# 3Phase_Inverter2.net
KiCad netlist of a schematic drawn in Altium Designer
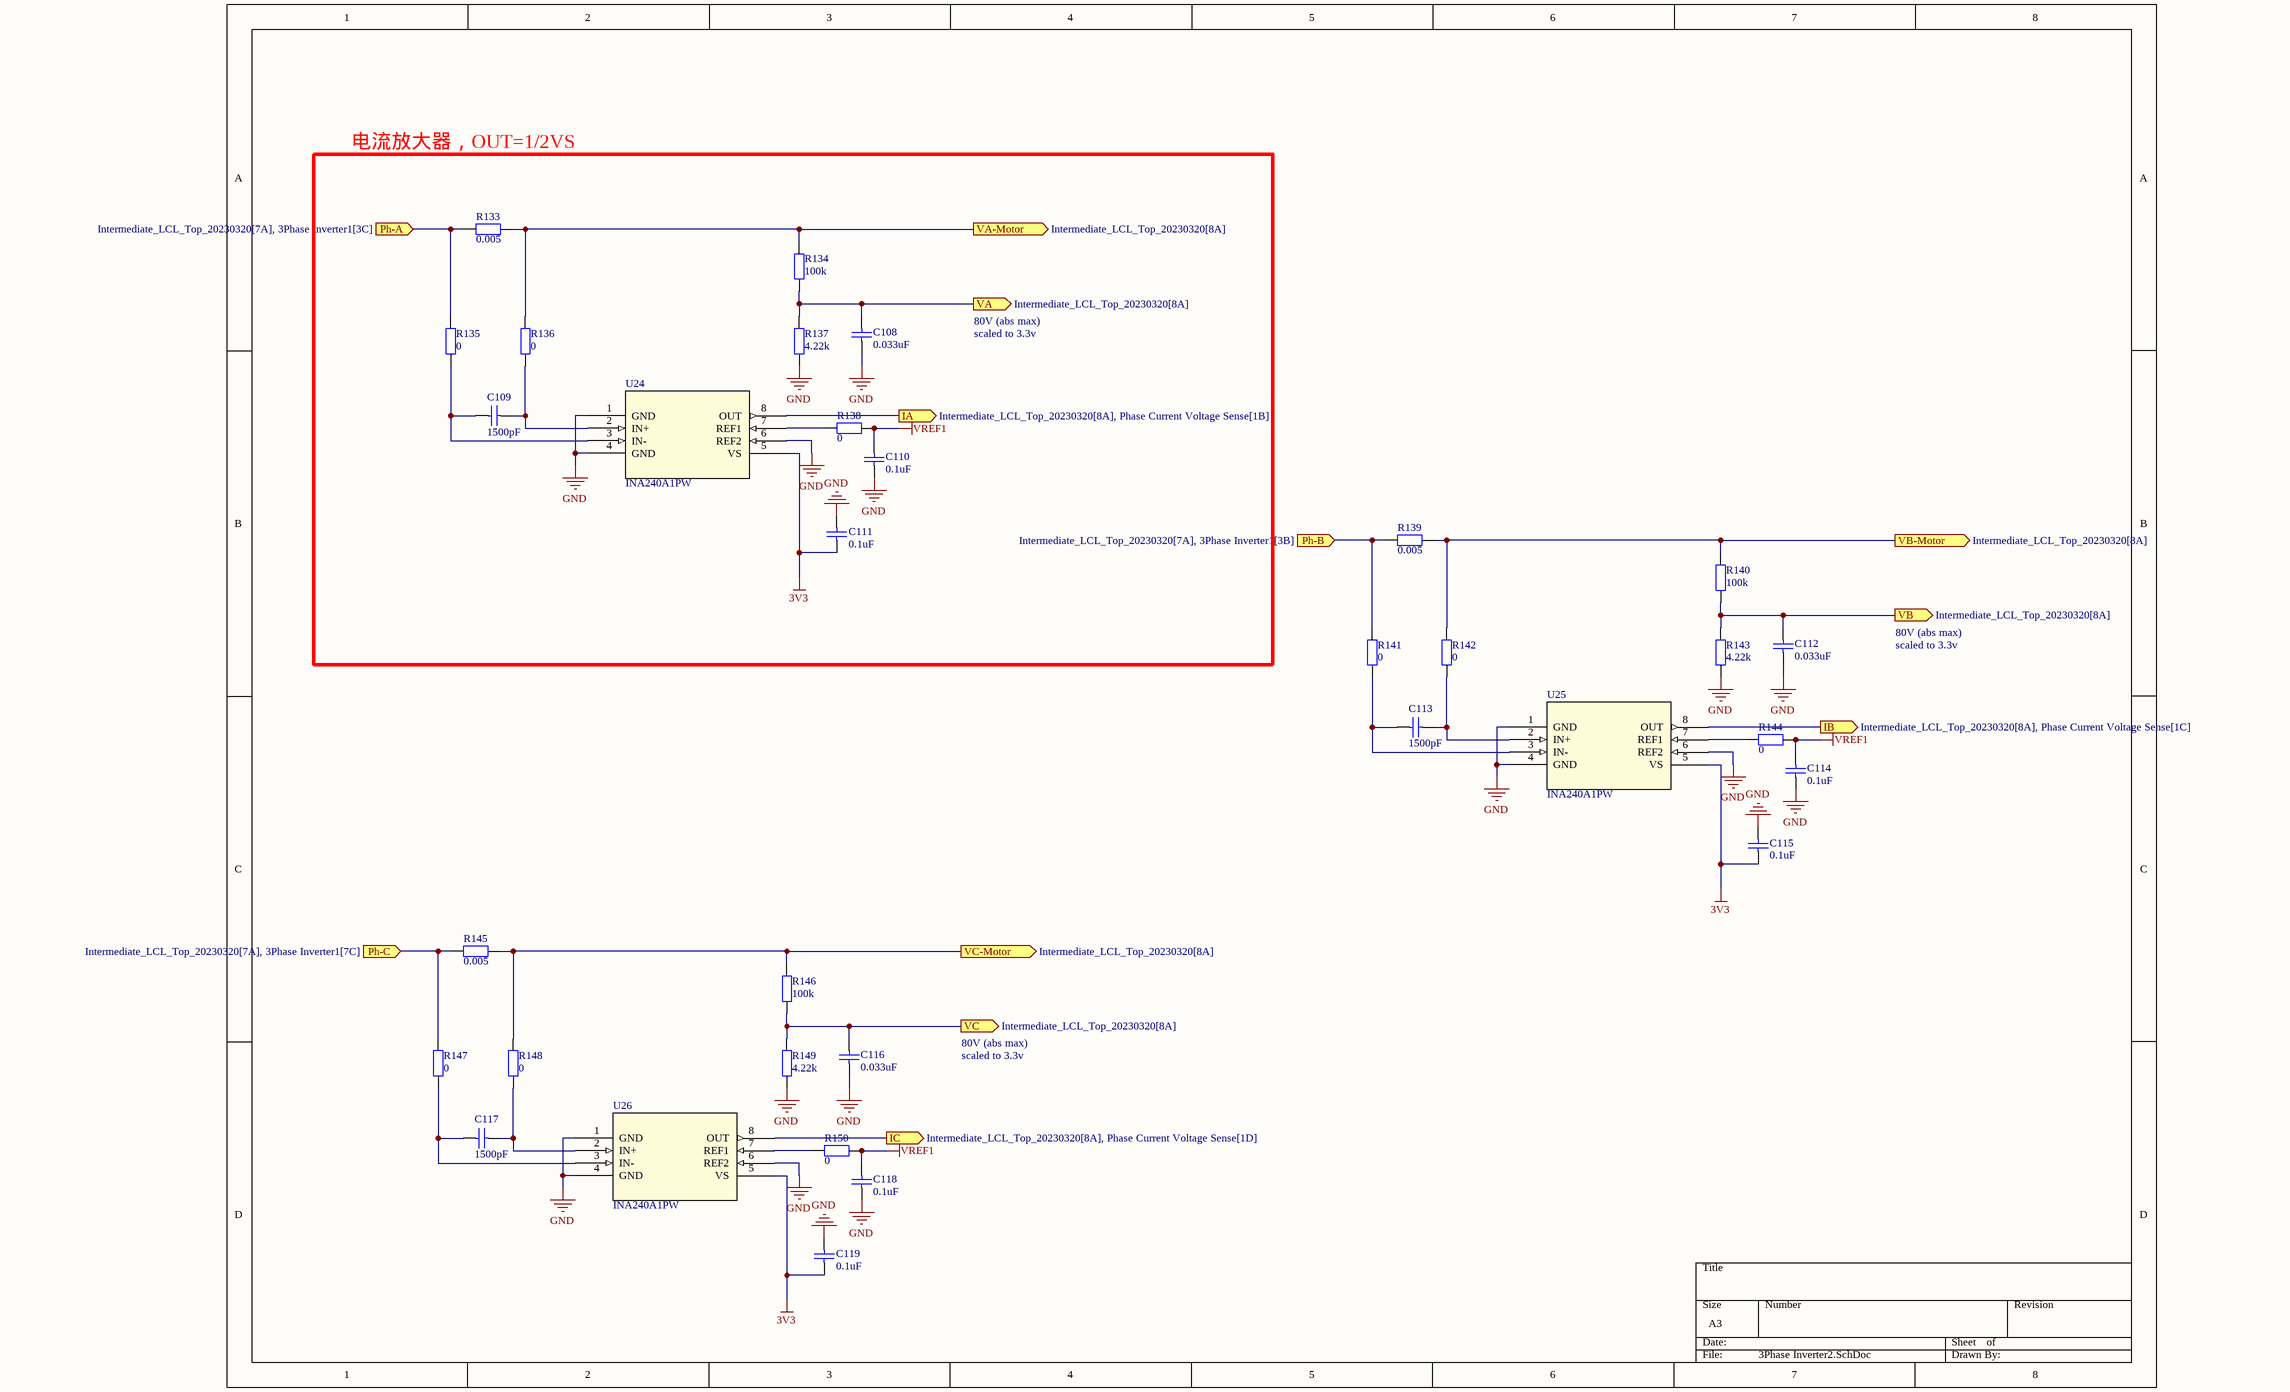
[diagram p0: 3Phase Inverter2.SchDoc]

(export (version "E")
  (design (tool "Eeschema 10.0.6"))
  (components
    (comp (ref "C108")
      (value "0.033uF")
      (footprint "CAPC1608X06N")
      (description "Capacitor")
      (fields (field (name "PUBLISHER") "Altium Limited"))
      (libsource (lib "Simscale") (part "Cap"))
    )
    (comp (ref "C109")
      (value "1500pF")
      (footprint "CAPC1608X06N")
      (description "Capacitor")
      (fields (field (name "PUBLISHER") "Altium Limited"))
      (libsource (lib "Simscale") (part "Cap"))
    )
    (comp (ref "C110")
      (value "0.1uF")
      (footprint "CAPC1608X06N")
      (description "Capacitor")
      (fields (field (name "PUBLISHER") "Altium Limited"))
      (libsource (lib "Simscale") (part "Cap"))
    )
    (comp (ref "C111")
      (value "0.1uF")
      (footprint "CAPC1608X06N")
      (description "Capacitor")
      (fields (field (name "PUBLISHER") "Altium Limited"))
      (libsource (lib "Simscale") (part "Cap"))
    )
    (comp (ref "C112")
      (value "0.033uF")
      (footprint "CAPC1608X06N")
      (description "Capacitor")
      (fields (field (name "PUBLISHER") "Altium Limited"))
      (libsource (lib "Simscale") (part "Cap"))
    )
    (comp (ref "C113")
      (value "1500pF")
      (footprint "CAPC1608X06N")
      (description "Capacitor")
      (fields (field (name "PUBLISHER") "Altium Limited"))
      (libsource (lib "Simscale") (part "Cap"))
    )
    (comp (ref "C114")
      (value "0.1uF")
      (footprint "CAPC1608X06N")
      (description "Capacitor")
      (fields (field (name "PUBLISHER") "Altium Limited"))
      (libsource (lib "Simscale") (part "Cap"))
    )
    (comp (ref "C115")
      (value "0.1uF")
      (footprint "CAPC1608X06N")
      (description "Capacitor")
      (fields (field (name "PUBLISHER") "Altium Limited"))
      (libsource (lib "Simscale") (part "Cap"))
    )
    (comp (ref "C116")
      (value "0.033uF")
      (footprint "CAPC1608X06N")
      (description "Capacitor")
      (fields (field (name "PUBLISHER") "Altium Limited"))
      (libsource (lib "Simscale") (part "Cap"))
    )
    (comp (ref "C117")
      (value "1500pF")
      (footprint "CAPC1608X06N")
      (description "Capacitor")
      (fields (field (name "PUBLISHER") "Altium Limited"))
      (libsource (lib "Simscale") (part "Cap"))
    )
    (comp (ref "C118")
      (value "0.1uF")
      (footprint "CAPC1608X06N")
      (description "Capacitor")
      (fields (field (name "PUBLISHER") "Altium Limited"))
      (libsource (lib "Simscale") (part "Cap"))
    )
    (comp (ref "C119")
      (value "0.1uF")
      (footprint "CAPC1608X06N")
      (description "Capacitor")
      (fields (field (name "PUBLISHER") "Altium Limited"))
      (libsource (lib "Simscale") (part "Cap"))
    )
    (comp (ref "R133")
      (value "0.005")
      (footprint "RESC1608X05N")
      (description "贴片电阻")
      (libsource (lib "") (part "0603 100KΩ (1003) 1%_4_2"))
    )
    (comp (ref "R134")
      (value "100k")
      (footprint "RESC1608X05N")
      (description "贴片电阻")
      (libsource (lib "") (part "0603 100KΩ (1003) 1%_4_1"))
    )
    (comp (ref "R135")
      (value "0")
      (footprint "RESC1608X05N")
      (description "贴片电阻")
      (libsource (lib "Simscale") (part "0603 100KΩ (1003) 1%_4"))
    )
    (comp (ref "R136")
      (value "0")
      (footprint "RESC1608X05N")
      (description "贴片电阻")
      (libsource (lib "Simscale") (part "0603 100KΩ (1003) 1%_4"))
    )
    (comp (ref "R137")
      (value "4.22k")
      (footprint "RESC1608X05N")
      (description "贴片电阻")
      (libsource (lib "") (part "0603 100KΩ (1003) 1%_4_1"))
    )
    (comp (ref "R138")
      (value "0")
      (footprint "RESC1608X05N")
      (description "贴片电阻")
      (libsource (lib "") (part "0603 100KΩ (1003) 1%_4_2"))
    )
    (comp (ref "R139")
      (value "0.005")
      (footprint "RESC1608X05N")
      (description "贴片电阻")
      (libsource (lib "") (part "0603 100KΩ (1003) 1%_4_2"))
    )
    (comp (ref "R140")
      (value "100k")
      (footprint "RESC1608X05N")
      (description "贴片电阻")
      (libsource (lib "") (part "0603 100KΩ (1003) 1%_4_1"))
    )
    (comp (ref "R141")
      (value "0")
      (footprint "RESC1608X05N")
      (description "贴片电阻")
      (libsource (lib "Simscale") (part "0603 100KΩ (1003) 1%_4"))
    )
    (comp (ref "R142")
      (value "0")
      (footprint "RESC1608X05N")
      (description "贴片电阻")
      (libsource (lib "Simscale") (part "0603 100KΩ (1003) 1%_4"))
    )
    (comp (ref "R143")
      (value "4.22k")
      (footprint "RESC1608X05N")
      (description "贴片电阻")
      (libsource (lib "") (part "0603 100KΩ (1003) 1%_4_1"))
    )
    (comp (ref "R144")
      (value "0")
      (footprint "RESC1608X05N")
      (description "贴片电阻")
      (libsource (lib "") (part "0603 100KΩ (1003) 1%_4_2"))
    )
    (comp (ref "R145")
      (value "0.005")
      (footprint "RESC1608X05N")
      (description "贴片电阻")
      (libsource (lib "") (part "0603 100KΩ (1003) 1%_4_2"))
    )
    (comp (ref "R146")
      (value "100k")
      (footprint "RESC1608X05N")
      (description "贴片电阻")
      (libsource (lib "") (part "0603 100KΩ (1003) 1%_4_1"))
    )
    (comp (ref "R147")
      (value "0")
      (footprint "RESC1608X05N")
      (description "贴片电阻")
      (libsource (lib "Simscale") (part "0603 100KΩ (1003) 1%_4"))
    )
    (comp (ref "R148")
      (value "0")
      (footprint "RESC1608X05N")
      (description "贴片电阻")
      (libsource (lib "Simscale") (part "0603 100KΩ (1003) 1%_4"))
    )
    (comp (ref "R149")
      (value "4.22k")
      (footprint "RESC1608X05N")
      (description "贴片电阻")
      (libsource (lib "") (part "0603 100KΩ (1003) 1%_4_1"))
    )
    (comp (ref "R150")
      (value "0")
      (footprint "RESC1608X05N")
      (description "贴片电阻")
      (libsource (lib "") (part "0603 100KΩ (1003) 1%_4_2"))
    )
    (comp (ref "U24")
      (value "INA240A1PW")
      (footprint "PW0008A_N_TEX")
      (description "No Description Available")
      (fields (field (name "COPYRIGHT") "Copyright (C) 2024 Ultra Librarian. All rights reserved."))
      (libsource (lib "aaa1") (part "INA240A1PW"))
    )
    (comp (ref "U25")
      (value "INA240A1PW")
      (footprint "PW0008A_N_TEX")
      (description "No Description Available")
      (fields (field (name "COPYRIGHT") "Copyright (C) 2024 Ultra Librarian. All rights reserved."))
      (libsource (lib "aaa1") (part "INA240A1PW"))
    )
    (comp (ref "U26")
      (value "INA240A1PW")
      (footprint "PW0008A_N_TEX")
      (description "No Description Available")
      (fields (field (name "COPYRIGHT") "Copyright (C) 2024 Ultra Librarian. All rights reserved."))
      (libsource (lib "aaa1") (part "INA240A1PW"))
    )
  )
  (nets
    (net (code "1") (name "/IA") (class "Default")
      (node (ref "U24") (pin "8") (pinfunction "OUT_8") (pintype "output"))
    )
    (net (code "2") (name "/IB") (class "Default")
      (node (ref "U25") (pin "8") (pinfunction "OUT_8") (pintype "output"))
    )
    (net (code "3") (name "/IC") (class "Default")
      (node (ref "U26") (pin "8") (pinfunction "OUT_8") (pintype "output"))
    )
    (net (code "4") (name "/Ph-A") (class "Default")
      (node (ref "R133") (pin "2") (pinfunction "2_2") (pintype "passive"))
      (node (ref "R135") (pin "1") (pinfunction "1_1") (pintype "passive"))
    )
    (net (code "5") (name "/Ph-B") (class "Default")
      (node (ref "R139") (pin "2") (pinfunction "2_2") (pintype "passive"))
      (node (ref "R141") (pin "1") (pinfunction "1_1") (pintype "passive"))
    )
    (net (code "6") (name "/Ph-C") (class "Default")
      (node (ref "R145") (pin "2") (pinfunction "2_2") (pintype "passive"))
      (node (ref "R147") (pin "1") (pinfunction "1_1") (pintype "passive"))
    )
    (net (code "7") (name "/VA") (class "Default")
      (node (ref "C108") (pin "1") (pinfunction "1_1") (pintype "passive"))
      (node (ref "R134") (pin "1") (pinfunction "1_1") (pintype "passive"))
      (node (ref "R137") (pin "2") (pinfunction "2_2") (pintype "passive"))
    )
    (net (code "8") (name "/VA-Motor") (class "Default")
      (node (ref "R133") (pin "1") (pinfunction "1_1") (pintype "passive"))
      (node (ref "R134") (pin "2") (pinfunction "2_2") (pintype "passive"))
      (node (ref "R136") (pin "1") (pinfunction "1_1") (pintype "passive"))
    )
    (net (code "9") (name "/VB") (class "Default")
      (node (ref "C112") (pin "1") (pinfunction "1_1") (pintype "passive"))
      (node (ref "R140") (pin "1") (pinfunction "1_1") (pintype "passive"))
      (node (ref "R143") (pin "2") (pinfunction "2_2") (pintype "passive"))
    )
    (net (code "10") (name "/VB-Motor") (class "Default")
      (node (ref "R139") (pin "1") (pinfunction "1_1") (pintype "passive"))
      (node (ref "R140") (pin "2") (pinfunction "2_2") (pintype "passive"))
      (node (ref "R142") (pin "1") (pinfunction "1_1") (pintype "passive"))
    )
    (net (code "11") (name "/VC") (class "Default")
      (node (ref "C116") (pin "1") (pinfunction "1_1") (pintype "passive"))
      (node (ref "R146") (pin "1") (pinfunction "1_1") (pintype "passive"))
      (node (ref "R149") (pin "2") (pinfunction "2_2") (pintype "passive"))
    )
    (net (code "12") (name "/VC-Motor") (class "Default")
      (node (ref "R145") (pin "1") (pinfunction "1_1") (pintype "passive"))
      (node (ref "R146") (pin "2") (pinfunction "2_2") (pintype "passive"))
      (node (ref "R148") (pin "1") (pinfunction "1_1") (pintype "passive"))
    )
    (net (code "13") (name "3V3") (class "Default")
      (node (ref "C111") (pin "2") (pinfunction "2_2") (pintype "passive"))
      (node (ref "C115") (pin "2") (pinfunction "2_2") (pintype "passive"))
      (node (ref "C119") (pin "2") (pinfunction "2_2") (pintype "passive"))
      (node (ref "U24") (pin "5") (pinfunction "VS_5") (pintype "power_in"))
      (node (ref "U25") (pin "5") (pinfunction "VS_5") (pintype "power_in"))
      (node (ref "U26") (pin "5") (pinfunction "VS_5") (pintype "power_in"))
    )
    (net (code "14") (name "GND") (class "Default")
      (node (ref "C108") (pin "2") (pinfunction "2_2") (pintype "passive"))
      (node (ref "C110") (pin "2") (pinfunction "2_2") (pintype "passive"))
      (node (ref "C111") (pin "1") (pinfunction "1_1") (pintype "passive"))
      (node (ref "C112") (pin "2") (pinfunction "2_2") (pintype "passive"))
      (node (ref "C114") (pin "2") (pinfunction "2_2") (pintype "passive"))
      (node (ref "C115") (pin "1") (pinfunction "1_1") (pintype "passive"))
      (node (ref "C116") (pin "2") (pinfunction "2_2") (pintype "passive"))
      (node (ref "C118") (pin "2") (pinfunction "2_2") (pintype "passive"))
      (node (ref "C119") (pin "1") (pinfunction "1_1") (pintype "passive"))
      (node (ref "R137") (pin "1") (pinfunction "1_1") (pintype "passive"))
      (node (ref "R143") (pin "1") (pinfunction "1_1") (pintype "passive"))
      (node (ref "R149") (pin "1") (pinfunction "1_1") (pintype "passive"))
      (node (ref "U24") (pin "1") (pinfunction "GND_1") (pintype "passive"))
      (node (ref "U24") (pin "4") (pinfunction "GND_4") (pintype "power_in"))
      (node (ref "U24") (pin "6") (pinfunction "REF2_6") (pintype "input"))
      (node (ref "U25") (pin "1") (pinfunction "GND_1") (pintype "passive"))
      (node (ref "U25") (pin "4") (pinfunction "GND_4") (pintype "power_in"))
      (node (ref "U25") (pin "6") (pinfunction "REF2_6") (pintype "input"))
      (node (ref "U26") (pin "1") (pinfunction "GND_1") (pintype "passive"))
      (node (ref "U26") (pin "4") (pinfunction "GND_4") (pintype "power_in"))
      (node (ref "U26") (pin "6") (pinfunction "REF2_6") (pintype "input"))
    )
    (net (code "15") (name "Net-(U24-IN+)") (class "Default")
      (node (ref "C109") (pin "1") (pinfunction "1_1") (pintype "passive"))
      (node (ref "R136") (pin "2") (pinfunction "2_2") (pintype "passive"))
      (node (ref "U24") (pin "2") (pinfunction "IN+_2") (pintype "input"))
    )
    (net (code "16") (name "Net-(U24-IN-)") (class "Default")
      (node (ref "C109") (pin "2") (pinfunction "2_2") (pintype "passive"))
      (node (ref "R135") (pin "2") (pinfunction "2_2") (pintype "passive"))
      (node (ref "U24") (pin "3") (pinfunction "IN-_3") (pintype "input"))
    )
    (net (code "17") (name "Net-(U24-REF1)") (class "Default")
      (node (ref "R138") (pin "2") (pinfunction "2_2") (pintype "passive"))
      (node (ref "U24") (pin "7") (pinfunction "REF1_7") (pintype "input"))
    )
    (net (code "18") (name "Net-(U25-IN+)") (class "Default")
      (node (ref "C113") (pin "1") (pinfunction "1_1") (pintype "passive"))
      (node (ref "R142") (pin "2") (pinfunction "2_2") (pintype "passive"))
      (node (ref "U25") (pin "2") (pinfunction "IN+_2") (pintype "input"))
    )
    (net (code "19") (name "Net-(U25-IN-)") (class "Default")
      (node (ref "C113") (pin "2") (pinfunction "2_2") (pintype "passive"))
      (node (ref "R141") (pin "2") (pinfunction "2_2") (pintype "passive"))
      (node (ref "U25") (pin "3") (pinfunction "IN-_3") (pintype "input"))
    )
    (net (code "20") (name "Net-(U25-REF1)") (class "Default")
      (node (ref "R144") (pin "2") (pinfunction "2_2") (pintype "passive"))
      (node (ref "U25") (pin "7") (pinfunction "REF1_7") (pintype "input"))
    )
    (net (code "21") (name "Net-(U26-IN+)") (class "Default")
      (node (ref "C117") (pin "1") (pinfunction "1_1") (pintype "passive"))
      (node (ref "R148") (pin "2") (pinfunction "2_2") (pintype "passive"))
      (node (ref "U26") (pin "2") (pinfunction "IN+_2") (pintype "input"))
    )
    (net (code "22") (name "Net-(U26-IN-)") (class "Default")
      (node (ref "C117") (pin "2") (pinfunction "2_2") (pintype "passive"))
      (node (ref "R147") (pin "2") (pinfunction "2_2") (pintype "passive"))
      (node (ref "U26") (pin "3") (pinfunction "IN-_3") (pintype "input"))
    )
    (net (code "23") (name "Net-(U26-REF1)") (class "Default")
      (node (ref "R150") (pin "2") (pinfunction "2_2") (pintype "passive"))
      (node (ref "U26") (pin "7") (pinfunction "REF1_7") (pintype "input"))
    )
    (net (code "24") (name "VREF1") (class "Default")
      (node (ref "C110") (pin "1") (pinfunction "1_1") (pintype "passive"))
      (node (ref "C114") (pin "1") (pinfunction "1_1") (pintype "passive"))
      (node (ref "C118") (pin "1") (pinfunction "1_1") (pintype "passive"))
      (node (ref "R138") (pin "1") (pinfunction "1_1") (pintype "passive"))
      (node (ref "R144") (pin "1") (pinfunction "1_1") (pintype "passive"))
      (node (ref "R150") (pin "1") (pinfunction "1_1") (pintype "passive"))
    )
  )
)
